# EurocardPowerSupply.net
KiCad netlist of a schematic drawn in EAGLE
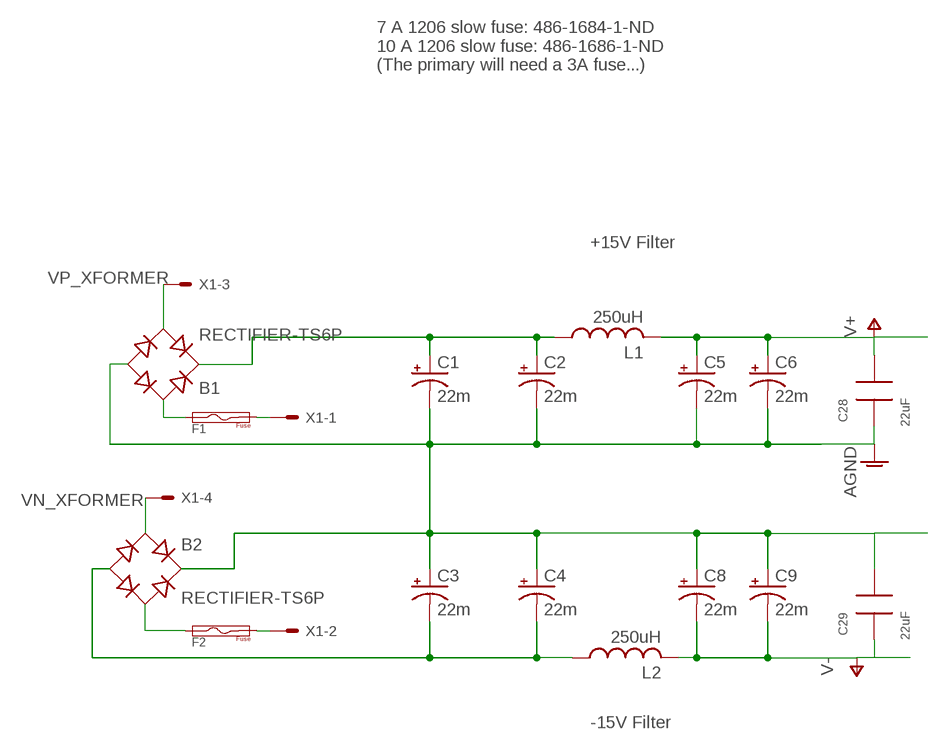
[diagram p0: schematic, sheet 1]
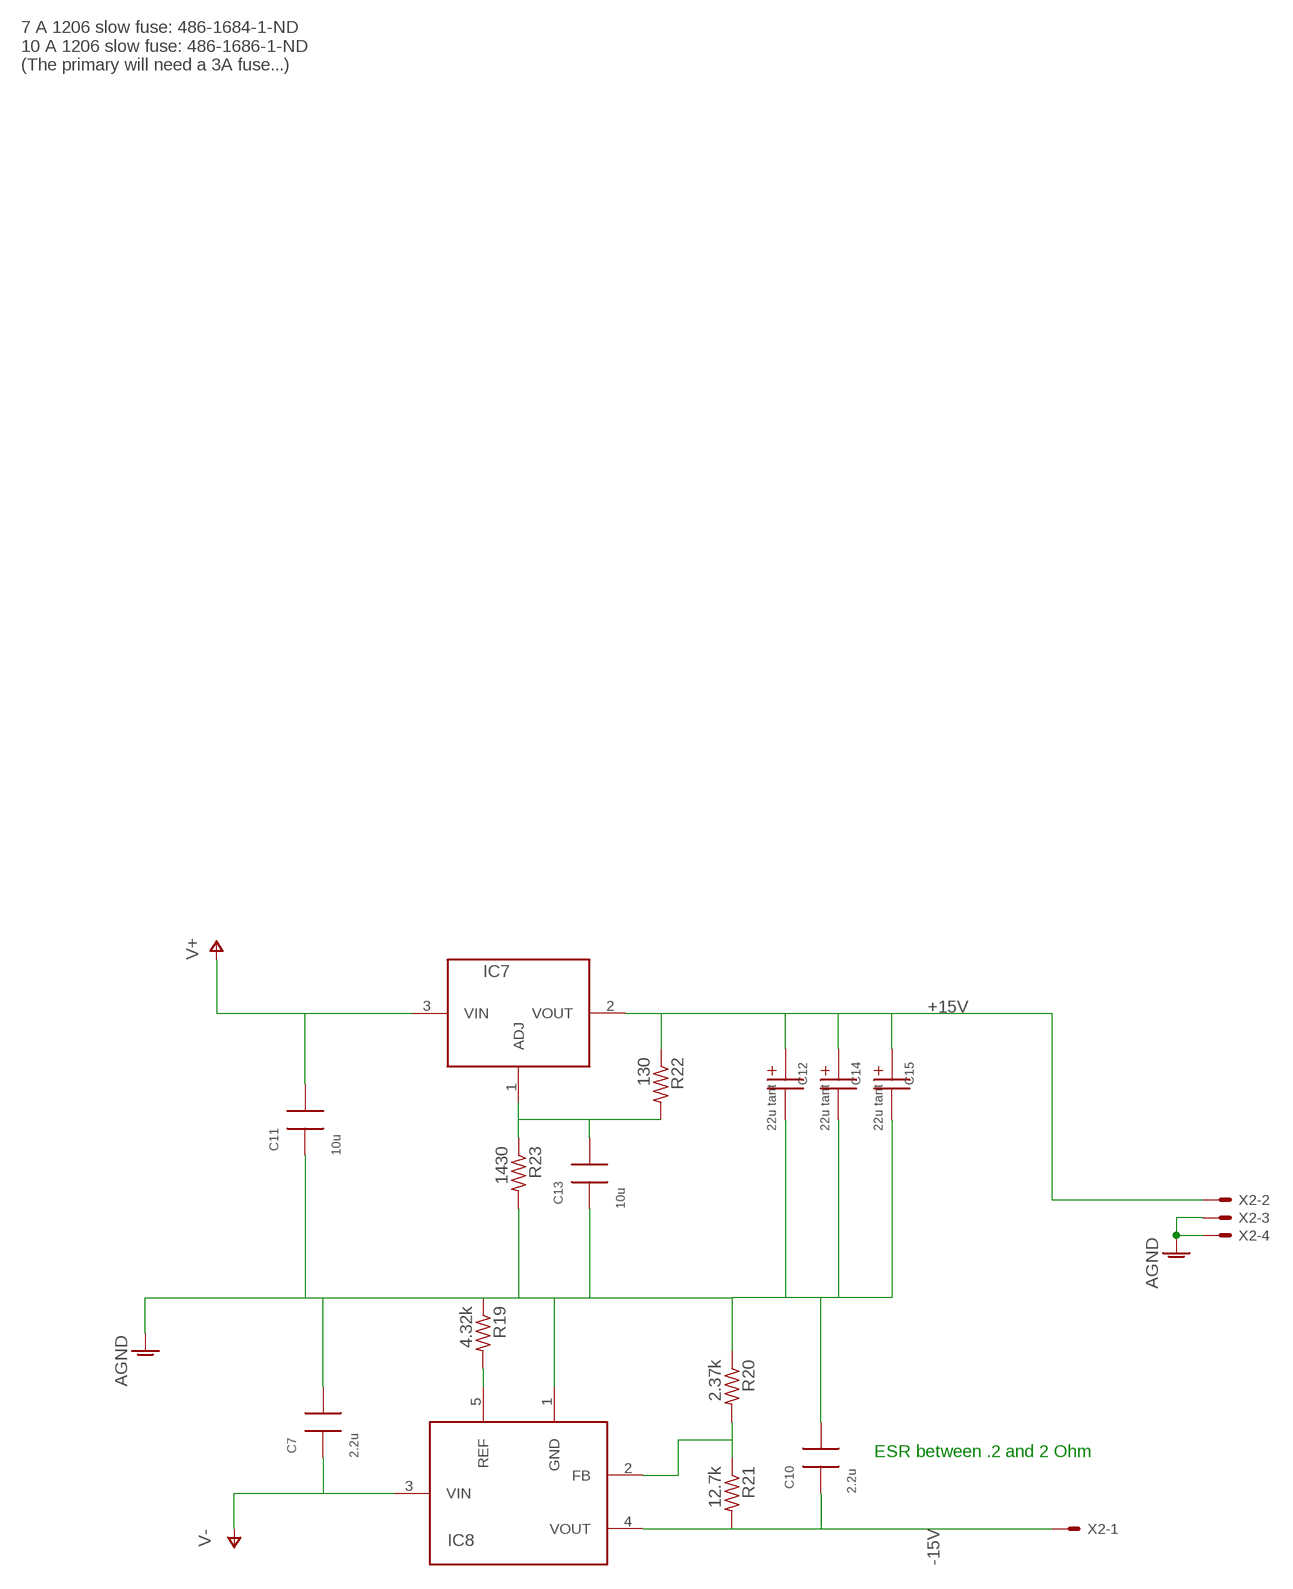
[diagram p1: schematic, sheet 2]
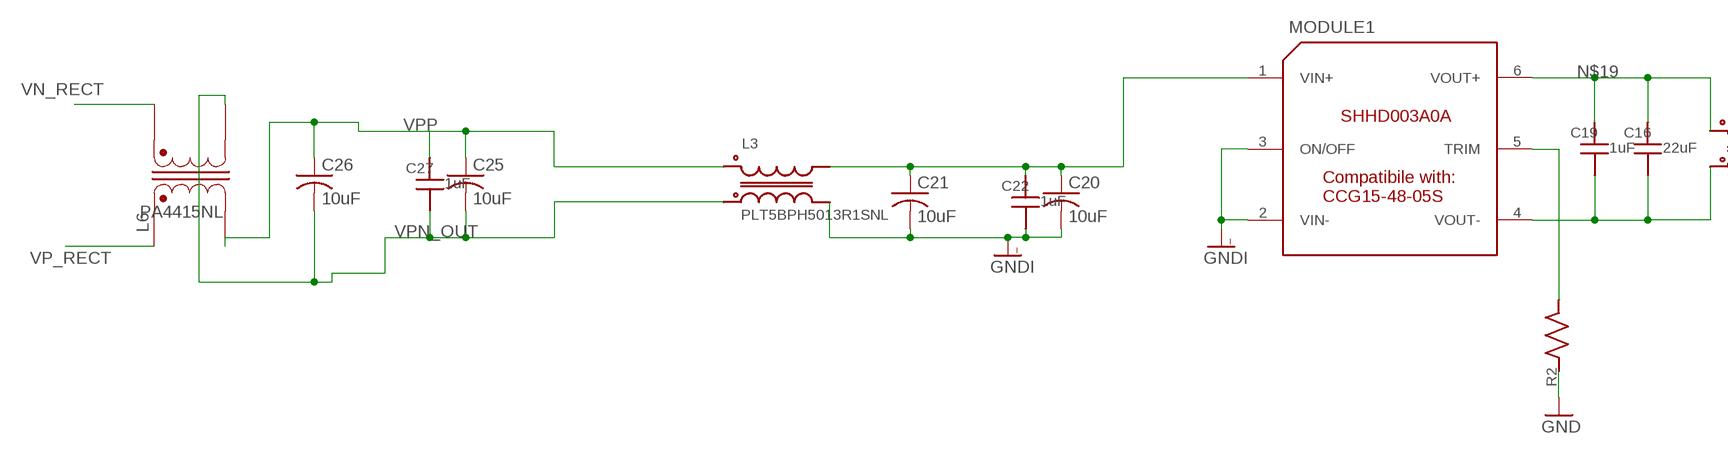
[diagram p2: schematic, sheet 3, part 1 of 2]
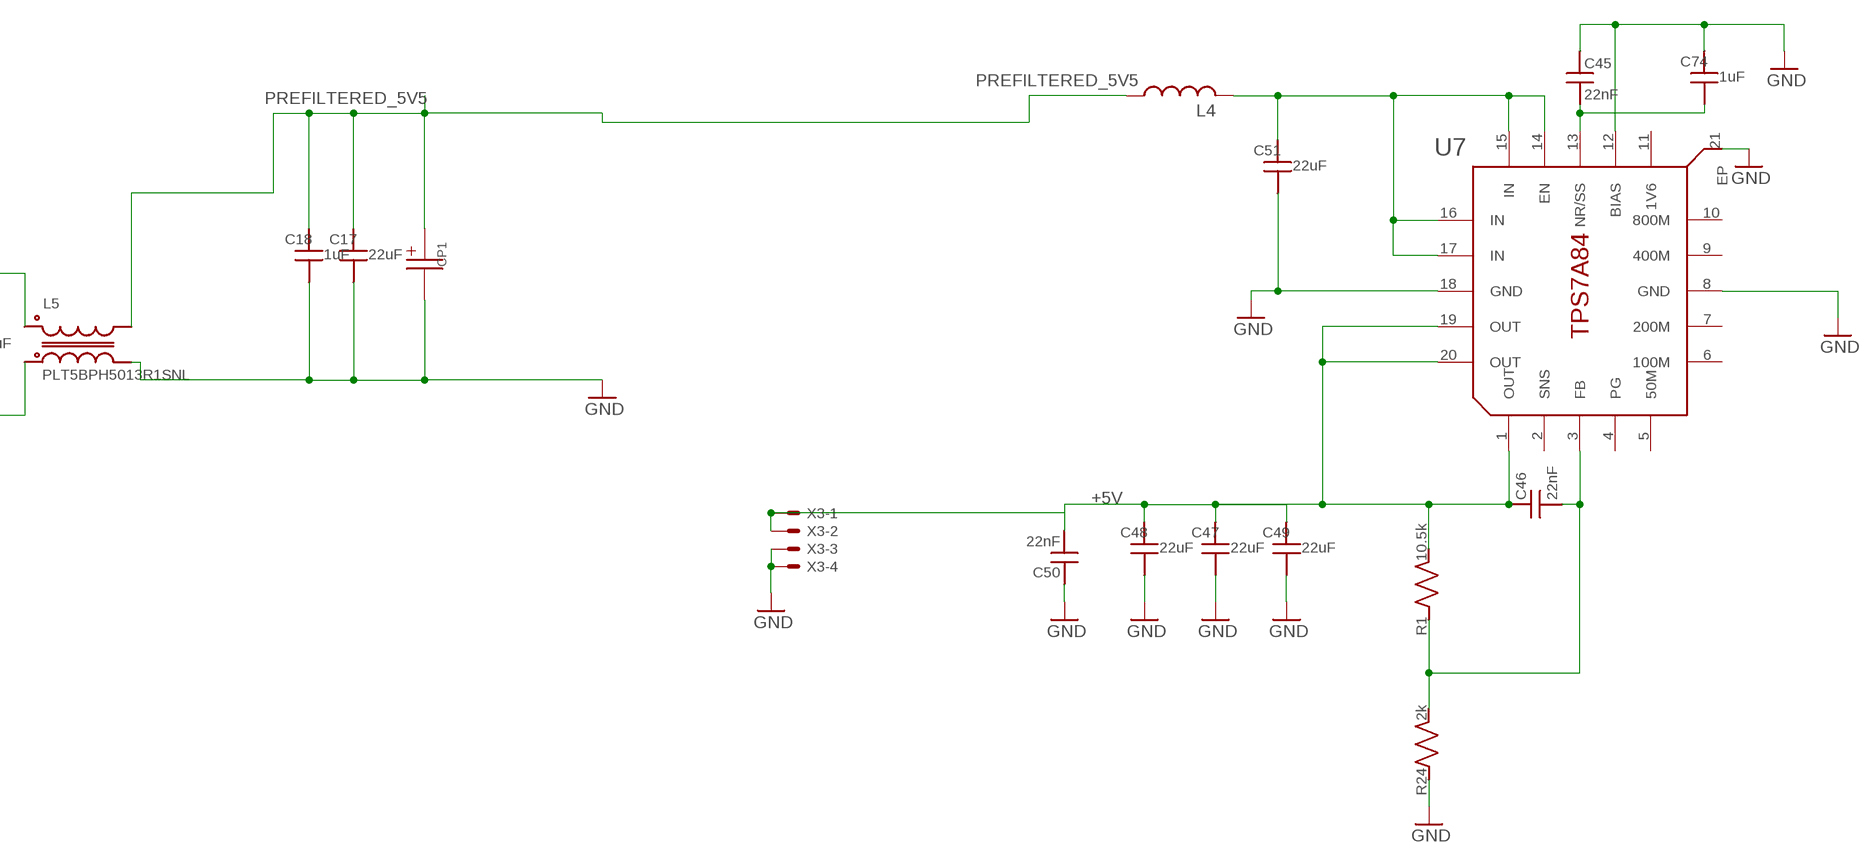
[diagram p3: schematic, sheet 3, part 2 of 2]

(export (version "E")
  (design (tool "Eeschema 10.0.6"))
  (components
    (comp (ref "C16")
      (value "22uF")
      (footprint "eagle-import:C_MLCC_0805")
      (libsource (lib "eagle-import") (part "C_MLCC_SMDCMLCC_0805"))
    )
    (comp (ref "C17")
      (value "22uF")
      (footprint "eagle-import:C_MLCC_0805")
      (libsource (lib "eagle-import") (part "C_MLCC_SMDCMLCC_0805"))
    )
    (comp (ref "C18")
      (value "1uF")
      (footprint "eagle-import:C_MLCC_0805")
      (libsource (lib "eagle-import") (part "C_MLCC_SMDCMLCC_0805"))
    )
    (comp (ref "C19")
      (value "1uF")
      (footprint "eagle-import:C_MLCC_0805")
      (libsource (lib "eagle-import") (part "C_MLCC_SMDCMLCC_0805"))
    )
    (comp (ref "C20")
      (value "10uF")
      (footprint "eagle-import:C2220K")
      (libsource (lib "eagle-import") (part "C-USC2220K"))
    )
    (comp (ref "C21")
      (value "10uF")
      (footprint "eagle-import:C2220K")
      (libsource (lib "eagle-import") (part "C-USC2220K"))
    )
    (comp (ref "C22")
      (value "1uF")
      (footprint "eagle-import:C_MLCC_0805")
      (libsource (lib "eagle-import") (part "C_MLCC_SMDCMLCC_0805"))
    )
    (comp (ref "C25")
      (value "10uF")
      (footprint "eagle-import:C2220K")
      (libsource (lib "eagle-import") (part "C-USC2220K"))
    )
    (comp (ref "C26")
      (value "10uF")
      (footprint "eagle-import:C2220K")
      (libsource (lib "eagle-import") (part "C-USC2220K"))
    )
    (comp (ref "C27")
      (value "1uF")
      (footprint "eagle-import:C_MLCC_0805")
      (libsource (lib "eagle-import") (part "C_MLCC_SMDCMLCC_0805"))
    )
    (comp (ref "C45")
      (value "22nF")
      (footprint "eagle-import:C_MLCC_0306")
      (libsource (lib "eagle-import") (part "C_MLCC_SMDCMLCC_0306"))
    )
    (comp (ref "C46")
      (value "22nF")
      (footprint "eagle-import:C_MLCC_0306")
      (libsource (lib "eagle-import") (part "C_MLCC_SMDCMLCC_0306"))
    )
    (comp (ref "C47")
      (value "22uF")
      (footprint "eagle-import:C_MLCC_0805")
      (libsource (lib "eagle-import") (part "C_MLCC_SMDCMLCC_0805"))
    )
    (comp (ref "C48")
      (value "22uF")
      (footprint "eagle-import:C_MLCC_0805")
      (libsource (lib "eagle-import") (part "C_MLCC_SMDCMLCC_0805"))
    )
    (comp (ref "C49")
      (value "22uF")
      (footprint "eagle-import:C_MLCC_0805")
      (libsource (lib "eagle-import") (part "C_MLCC_SMDCMLCC_0805"))
    )
    (comp (ref "C50")
      (value "22nF")
      (footprint "eagle-import:C_MLCC_0306")
      (libsource (lib "eagle-import") (part "C_MLCC_SMDCMLCC_0306"))
    )
    (comp (ref "C51")
      (value "22uF")
      (footprint "eagle-import:C_MLCC_0805")
      (libsource (lib "eagle-import") (part "C_MLCC_SMDCMLCC_0805"))
    )
    (comp (ref "C74")
      (value "1uF")
      (footprint "eagle-import:C_MLCC_0805")
      (libsource (lib "eagle-import") (part "C_MLCC_SMDCMLCC_0805"))
    )
    (comp (ref "CP1")
      (value "CAP-POLPANASONIC_F")
      (footprint "eagle-import:PANASONIC_F")
      (libsource (lib "eagle-import") (part "CAP-POLPANASONIC_F"))
    )
    (comp (ref "L3")
      (value "PLT5BPH5013R1SNL")
      (footprint "eagle-import:MURATA_CM_CHOKE_PLT5BPH_SERIES")
      (libsource (lib "eagle-import") (part "MURATA_CM_COIL_SERIES_PLT5BPH"))
    )
    (comp (ref "L4")
      (value "MURATA_NFZ5BBW100LN10L")
      (footprint "eagle-import:MURATA_1MHZ_3A_FERRITE")
      (libsource (lib "eagle-import") (part "MURATA_NFZ5BBW100LN10L"))
    )
    (comp (ref "L5")
      (value "PLT5BPH5013R1SNL")
      (footprint "eagle-import:MURATA_CM_CHOKE_PLT5BPH_SERIES")
      (libsource (lib "eagle-import") (part "MURATA_CM_COIL_SERIES_PLT5BPH"))
    )
    (comp (ref "L6")
      (value "PA4415NL")
      (footprint "eagle-import:PA4415NL")
      (libsource (lib "eagle-import") (part "PA4415NL"))
    )
    (comp (ref "MODULE1")
      (value "GE_SHHD003A0A")
      (footprint "eagle-import:GE_SHHD003A0A_THROUGH_HOLE")
      (libsource (lib "eagle-import") (part "GE_SHHD003A0A"))
    )
    (comp (ref "R1")
      (value "10.5k")
      (footprint "eagle-import:R_0805")
      (libsource (lib "eagle-import") (part "R_SMDR0805"))
    )
    (comp (ref "R2")
      (value "R_SMDR0805")
      (footprint "eagle-import:R_0805")
      (libsource (lib "eagle-import") (part "R_SMDR0805"))
    )
    (comp (ref "R24")
      (value "2k")
      (footprint "eagle-import:R_0805")
      (libsource (lib "eagle-import") (part "R_SMDR0805"))
    )
    (comp (ref "U7")
      (value "TEXAS_INSTRUMENTS_TPS7A84")
      (footprint "eagle-import:S-PVQFN-N20")
      (libsource (lib "eagle-import") (part "TEXAS_INSTRUMENTS_TPS7A84"))
    )
    (comp (ref "X3")
      (value "5566-4")
      (footprint "eagle-import:5566-4")
      (libsource (lib "eagle-import") (part "5566-4"))
    )
    (comp (ref "B1")
      (value "RECTIFIER-TS6P")
      (footprint "eagle-import:TS6P")
      (libsource (lib "eagle-import") (part "RECTIFIER-TS6P"))
    )
    (comp (ref "B2")
      (value "RECTIFIER-TS6P")
      (footprint "eagle-import:TS6P")
      (libsource (lib "eagle-import") (part "RECTIFIER-TS6P"))
    )
    (comp (ref "C1")
      (value "22m")
      (footprint "eagle-import:EB35D")
      (libsource (lib "eagle-import") (part "CPOL-USEB35D"))
    )
    (comp (ref "C2")
      (value "22m")
      (footprint "eagle-import:EB35D")
      (libsource (lib "eagle-import") (part "CPOL-USEB35D"))
    )
    (comp (ref "C3")
      (value "22m")
      (footprint "eagle-import:EB35D")
      (libsource (lib "eagle-import") (part "CPOL-USEB35D"))
    )
    (comp (ref "C4")
      (value "22m")
      (footprint "eagle-import:EB35D")
      (libsource (lib "eagle-import") (part "CPOL-USEB35D"))
    )
    (comp (ref "C5")
      (value "22m")
      (footprint "eagle-import:EB35D")
      (libsource (lib "eagle-import") (part "CPOL-USEB35D"))
    )
    (comp (ref "C6")
      (value "22m")
      (footprint "eagle-import:EB35D")
      (libsource (lib "eagle-import") (part "CPOL-USEB35D"))
    )
    (comp (ref "C8")
      (value "22m")
      (footprint "eagle-import:EB35D")
      (libsource (lib "eagle-import") (part "CPOL-USEB35D"))
    )
    (comp (ref "C9")
      (value "22m")
      (footprint "eagle-import:EB35D")
      (libsource (lib "eagle-import") (part "CPOL-USEB35D"))
    )
    (comp (ref "C28")
      (value "22uF")
      (footprint "eagle-import:1206")
      (libsource (lib "eagle-import") (part "CAP1206"))
    )
    (comp (ref "C29")
      (value "22uF")
      (footprint "eagle-import:1206")
      (libsource (lib "eagle-import") (part "CAP1206"))
    )
    (comp (ref "F1")
      (value "FUSE1206")
      (footprint "eagle-import:FUSE1206")
      (libsource (lib "eagle-import") (part "FUSE1206"))
    )
    (comp (ref "F2")
      (value "FUSE1206")
      (footprint "eagle-import:FUSE1206")
      (libsource (lib "eagle-import") (part "FUSE1206"))
    )
    (comp (ref "L1")
      (value "250uH")
      (footprint "eagle-import:5721-RC")
      (libsource (lib "eagle-import") (part "INDUCTOR5721-RC"))
    )
    (comp (ref "L2")
      (value "250uH")
      (footprint "eagle-import:5721-RC")
      (libsource (lib "eagle-import") (part "INDUCTOR5721-RC"))
    )
    (comp (ref "X1")
      (value "5566-4")
      (footprint "eagle-import:5566-4")
      (libsource (lib "eagle-import") (part "5566-4"))
    )
    (comp (ref "C7")
      (value "2.2u")
      (footprint "eagle-import:1206")
      (libsource (lib "eagle-import") (part "CAP1206"))
    )
    (comp (ref "C10")
      (value "2.2u")
      (footprint "eagle-import:1206")
      (libsource (lib "eagle-import") (part "CAP1206"))
    )
    (comp (ref "C11")
      (value "10u")
      (footprint "eagle-import:1206")
      (libsource (lib "eagle-import") (part "CAP1206"))
    )
    (comp (ref "C12")
      (value "22u tant")
      (footprint "eagle-import:1206P")
      (libsource (lib "eagle-import") (part "rlc-jqi_CAP-POL1206"))
    )
    (comp (ref "C13")
      (value "10u")
      (footprint "eagle-import:1206")
      (libsource (lib "eagle-import") (part "CAP1206"))
    )
    (comp (ref "C14")
      (value "22u tant")
      (footprint "eagle-import:1206P")
      (libsource (lib "eagle-import") (part "rlc-jqi_CAP-POL1206"))
    )
    (comp (ref "C15")
      (value "22u tant")
      (footprint "eagle-import:1206P")
      (libsource (lib "eagle-import") (part "rlc-jqi_CAP-POL1206"))
    )
    (comp (ref "IC7")
      (value "LM1084TO220")
      (footprint "eagle-import:T03B")
      (libsource (lib "eagle-import") (part "LM1084TO220"))
    )
    (comp (ref "IC8")
      (value "LT1185TO220/INLINE")
      (footprint "eagle-import:T05A")
      (libsource (lib "eagle-import") (part "LT1185TO220/INLINE"))
    )
    (comp (ref "R19")
      (value "4.32k")
      (footprint "eagle-import:R1206")
      (libsource (lib "eagle-import") (part "R-US_R1206"))
    )
    (comp (ref "R20")
      (value "2.37k")
      (footprint "eagle-import:R1206")
      (libsource (lib "eagle-import") (part "R-US_R1206"))
    )
    (comp (ref "R21")
      (value "12.7k")
      (footprint "eagle-import:R1206")
      (libsource (lib "eagle-import") (part "R-US_R1206"))
    )
    (comp (ref "R22")
      (value "130")
      (footprint "eagle-import:R1206")
      (libsource (lib "eagle-import") (part "R-US_R1206"))
    )
    (comp (ref "R23")
      (value "1430")
      (footprint "eagle-import:R1206")
      (libsource (lib "eagle-import") (part "R-US_R1206"))
    )
    (comp (ref "X2")
      (value "5566-4")
      (footprint "eagle-import:5566-4")
      (libsource (lib "eagle-import") (part "5566-4"))
    )
  )
  (nets
    (net (code "1") (name "+5V") (class "Default")
      (node (ref "C46") (pin "P$1") (pinfunction "1_P$1") (pintype "passive"))
      (node (ref "C47") (pin "P$1") (pinfunction "1_P$1") (pintype "passive"))
      (node (ref "C48") (pin "P$1") (pinfunction "1_P$1") (pintype "passive"))
      (node (ref "C49") (pin "P$1") (pinfunction "1_P$1") (pintype "passive"))
      (node (ref "C50") (pin "P$2") (pinfunction "2_P$2") (pintype "passive"))
      (node (ref "R1") (pin "P$2") (pinfunction "2_P$2") (pintype "passive"))
      (node (ref "U7") (pin "1") (pinfunction "OUT_1") (pintype "bidirectional"))
      (node (ref "U7") (pin "19") (pinfunction "OUT_19") (pintype "bidirectional"))
      (node (ref "U7") (pin "20") (pinfunction "OUT_20") (pintype "bidirectional"))
      (node (ref "X3") (pin "1") (pinfunction "S_1") (pintype "passive"))
      (node (ref "X3") (pin "2") (pinfunction "S_2") (pintype "passive"))
    )
    (net (code "2") (name "+15V") (class "Default")
      (node (ref "C12") (pin "1") (pinfunction "P$1_1") (pintype "passive"))
      (node (ref "C14") (pin "1") (pinfunction "P$1_1") (pintype "passive"))
      (node (ref "C15") (pin "1") (pinfunction "P$1_1") (pintype "passive"))
      (node (ref "IC7") (pin "2") (pinfunction "VOUT_2") (pintype "bidirectional"))
      (node (ref "R22") (pin "1") (pinfunction "1_1") (pintype "passive"))
      (node (ref "X2") (pin "2") (pinfunction "S_2") (pintype "passive"))
    )
    (net (code "3") (name "-15V") (class "Default")
      (node (ref "C10") (pin "1") (pinfunction "P$1_1") (pintype "passive"))
      (node (ref "IC8") (pin "4") (pinfunction "VOUT_4") (pintype "bidirectional"))
      (node (ref "R21") (pin "2") (pinfunction "2_2") (pintype "passive"))
      (node (ref "X2") (pin "1") (pinfunction "S_1") (pintype "passive"))
    )
    (net (code "4") (name "AGND") (class "Default")
      (node (ref "B1") (pin "-") (pinfunction "-_-") (pintype "passive"))
      (node (ref "B2") (pin "+") (pinfunction "+_+") (pintype "passive"))
      (node (ref "C1") (pin "-") (pinfunction "-_-") (pintype "passive"))
      (node (ref "C10") (pin "2") (pinfunction "P$2_2") (pintype "passive"))
      (node (ref "C11") (pin "1") (pinfunction "P$1_1") (pintype "passive"))
      (node (ref "C12") (pin "2") (pinfunction "P$2_2") (pintype "passive"))
      (node (ref "C13") (pin "1") (pinfunction "P$1_1") (pintype "passive"))
      (node (ref "C14") (pin "2") (pinfunction "P$2_2") (pintype "passive"))
      (node (ref "C15") (pin "2") (pinfunction "P$2_2") (pintype "passive"))
      (node (ref "C2") (pin "-") (pinfunction "-_-") (pintype "passive"))
      (node (ref "C28") (pin "1") (pinfunction "P$1_1") (pintype "passive"))
      (node (ref "C29") (pin "2") (pinfunction "P$2_2") (pintype "passive"))
      (node (ref "C3") (pin "+") (pinfunction "+_+") (pintype "passive"))
      (node (ref "C4") (pin "+") (pinfunction "+_+") (pintype "passive"))
      (node (ref "C5") (pin "-") (pinfunction "-_-") (pintype "passive"))
      (node (ref "C6") (pin "-") (pinfunction "-_-") (pintype "passive"))
      (node (ref "C7") (pin "2") (pinfunction "P$2_2") (pintype "passive"))
      (node (ref "C8") (pin "+") (pinfunction "+_+") (pintype "passive"))
      (node (ref "C9") (pin "+") (pinfunction "+_+") (pintype "passive"))
      (node (ref "IC8") (pin "1") (pinfunction "GND_1") (pintype "bidirectional"))
      (node (ref "R19") (pin "1") (pinfunction "1_1") (pintype "passive"))
      (node (ref "R20") (pin "1") (pinfunction "1_1") (pintype "passive"))
      (node (ref "R23") (pin "2") (pinfunction "2_2") (pintype "passive"))
      (node (ref "X2") (pin "3") (pinfunction "S_3") (pintype "passive"))
      (node (ref "X2") (pin "4") (pinfunction "S_4") (pintype "passive"))
    )
    (net (code "5") (name "GND") (class "Default")
      (node (ref "C17") (pin "P$2") (pinfunction "2_P$2") (pintype "passive"))
      (node (ref "C18") (pin "P$2") (pinfunction "2_P$2") (pintype "passive"))
      (node (ref "C45") (pin "P$1") (pinfunction "1_P$1") (pintype "passive"))
      (node (ref "C47") (pin "P$2") (pinfunction "2_P$2") (pintype "passive"))
      (node (ref "C48") (pin "P$2") (pinfunction "2_P$2") (pintype "passive"))
      (node (ref "C49") (pin "P$2") (pinfunction "2_P$2") (pintype "passive"))
      (node (ref "C50") (pin "P$1") (pinfunction "1_P$1") (pintype "passive"))
      (node (ref "C51") (pin "P$2") (pinfunction "2_P$2") (pintype "passive"))
      (node (ref "C74") (pin "P$1") (pinfunction "1_P$1") (pintype "passive"))
      (node (ref "CP1") (pin "-") (pinfunction "P$2_-") (pintype "passive"))
      (node (ref "L5") (pin "P$3") (pinfunction "3_P$3") (pintype "passive"))
      (node (ref "R2") (pin "P$1") (pinfunction "1_P$1") (pintype "passive"))
      (node (ref "R24") (pin "P$1") (pinfunction "1_P$1") (pintype "passive"))
      (node (ref "U7") (pin "12") (pinfunction "BIAS_12") (pintype "bidirectional"))
      (node (ref "U7") (pin "18") (pinfunction "GND_18") (pintype "bidirectional"))
      (node (ref "U7") (pin "21") (pinfunction "EP_21") (pintype "bidirectional"))
      (node (ref "U7") (pin "8") (pinfunction "GND_8") (pintype "bidirectional"))
      (node (ref "X3") (pin "3") (pinfunction "S_3") (pintype "passive"))
      (node (ref "X3") (pin "4") (pinfunction "S_4") (pintype "passive"))
    )
    (net (code "6") (name "GNDI") (class "Default")
      (node (ref "C20") (pin "2") (pinfunction "2_2") (pintype "passive"))
      (node (ref "C21") (pin "2") (pinfunction "2_2") (pintype "passive"))
      (node (ref "C22") (pin "P$2") (pinfunction "2_P$2") (pintype "passive"))
      (node (ref "L3") (pin "P$3") (pinfunction "3_P$3") (pintype "passive"))
      (node (ref "MODULE1") (pin "2") (pinfunction "VIN-_2") (pintype "bidirectional"))
      (node (ref "MODULE1") (pin "3") (pinfunction "ON/OFF_3") (pintype "bidirectional"))
    )
    (net (code "7") (name "N$19") (class "Default")
      (node (ref "C16") (pin "P$1") (pinfunction "1_P$1") (pintype "passive"))
      (node (ref "C19") (pin "P$1") (pinfunction "1_P$1") (pintype "passive"))
      (node (ref "L5") (pin "P$1") (pinfunction "2_P$1") (pintype "passive"))
      (node (ref "MODULE1") (pin "6") (pinfunction "VOUT+_6") (pintype "bidirectional"))
    )
    (net (code "8") (name "Net-(C13-P$2)") (class "Default")
      (node (ref "C13") (pin "2") (pinfunction "P$2_2") (pintype "passive"))
      (node (ref "IC7") (pin "1") (pinfunction "ADJ_1") (pintype "bidirectional"))
      (node (ref "R22") (pin "2") (pinfunction "2_2") (pintype "passive"))
      (node (ref "R23") (pin "1") (pinfunction "1_1") (pintype "passive"))
    )
    (net (code "9") (name "Net-(C16-2)") (class "Default")
      (node (ref "C16") (pin "P$2") (pinfunction "2_P$2") (pintype "passive"))
      (node (ref "C19") (pin "P$2") (pinfunction "2_P$2") (pintype "passive"))
      (node (ref "L5") (pin "P$4") (pinfunction "1_P$4") (pintype "passive"))
      (node (ref "MODULE1") (pin "4") (pinfunction "VOUT-_4") (pintype "bidirectional"))
    )
    (net (code "10") (name "Net-(C22-1)") (class "Default")
      (node (ref "C20") (pin "1") (pinfunction "1_1") (pintype "passive"))
      (node (ref "C21") (pin "1") (pinfunction "1_1") (pintype "passive"))
      (node (ref "C22") (pin "P$1") (pinfunction "1_P$1") (pintype "passive"))
      (node (ref "L3") (pin "P$2") (pinfunction "4_P$2") (pintype "passive"))
      (node (ref "MODULE1") (pin "1") (pinfunction "VIN+_1") (pintype "bidirectional"))
    )
    (net (code "11") (name "Net-(C45-2)") (class "Default")
      (node (ref "C45") (pin "P$2") (pinfunction "2_P$2") (pintype "passive"))
      (node (ref "C74") (pin "P$2") (pinfunction "2_P$2") (pintype "passive"))
      (node (ref "U7") (pin "13") (pinfunction "NR/SS_13") (pintype "bidirectional"))
    )
    (net (code "12") (name "Net-(C46-2)") (class "Default")
      (node (ref "C46") (pin "P$2") (pinfunction "2_P$2") (pintype "passive"))
      (node (ref "R1") (pin "P$1") (pinfunction "1_P$1") (pintype "passive"))
      (node (ref "R24") (pin "P$2") (pinfunction "2_P$2") (pintype "passive"))
      (node (ref "U7") (pin "3") (pinfunction "FB_3") (pintype "bidirectional"))
    )
    (net (code "13") (name "Net-(C51-1)") (class "Default")
      (node (ref "C51") (pin "P$1") (pinfunction "1_P$1") (pintype "passive"))
      (node (ref "L4") (pin "P$2") (pinfunction "2_P$2") (pintype "passive"))
      (node (ref "U7") (pin "14") (pinfunction "EN_14") (pintype "bidirectional"))
      (node (ref "U7") (pin "15") (pinfunction "IN_15") (pintype "bidirectional"))
      (node (ref "U7") (pin "16") (pinfunction "IN_16") (pintype "bidirectional"))
      (node (ref "U7") (pin "17") (pinfunction "IN_17") (pintype "bidirectional"))
    )
    (net (code "14") (name "Net-(F1-P$1)") (class "Default")
      (node (ref "B1") (pin "AC1") (pinfunction "AC1_AC1") (pintype "passive"))
      (node (ref "F1") (pin "1") (pinfunction "P$1_1") (pintype "bidirectional"))
    )
    (net (code "15") (name "Net-(F1-P$2)") (class "Default")
      (node (ref "F1") (pin "2") (pinfunction "P$2_2") (pintype "bidirectional"))
      (node (ref "X1") (pin "1") (pinfunction "S_1") (pintype "passive"))
    )
    (net (code "16") (name "Net-(F2-P$1)") (class "Default")
      (node (ref "B2") (pin "AC2") (pinfunction "AC2_AC2") (pintype "passive"))
      (node (ref "F2") (pin "1") (pinfunction "P$1_1") (pintype "bidirectional"))
    )
    (net (code "17") (name "Net-(F2-P$2)") (class "Default")
      (node (ref "F2") (pin "2") (pinfunction "P$2_2") (pintype "bidirectional"))
      (node (ref "X1") (pin "2") (pinfunction "S_2") (pintype "passive"))
    )
    (net (code "18") (name "Net-(IC8-FB)") (class "Default")
      (node (ref "IC8") (pin "2") (pinfunction "FB_2") (pintype "bidirectional"))
      (node (ref "R20") (pin "2") (pinfunction "2_2") (pintype "passive"))
      (node (ref "R21") (pin "1") (pinfunction "1_1") (pintype "passive"))
    )
    (net (code "19") (name "Net-(IC8-REF)") (class "Default")
      (node (ref "IC8") (pin "5") (pinfunction "REF_5") (pintype "bidirectional"))
      (node (ref "R19") (pin "2") (pinfunction "2_2") (pintype "passive"))
    )
    (net (code "20") (name "Net-(MODULE1-TRIM)") (class "Default")
      (node (ref "MODULE1") (pin "5") (pinfunction "TRIM_5") (pintype "bidirectional"))
      (node (ref "R2") (pin "P$2") (pinfunction "2_P$2") (pintype "passive"))
    )
    (net (code "21") (name "PREFILTERED_5V5") (class "Default")
      (node (ref "C17") (pin "P$1") (pinfunction "1_P$1") (pintype "passive"))
      (node (ref "C18") (pin "P$1") (pinfunction "1_P$1") (pintype "passive"))
      (node (ref "CP1") (pin "+") (pinfunction "P$1_+") (pintype "passive"))
      (node (ref "L4") (pin "P$1") (pinfunction "1_P$1") (pintype "passive"))
      (node (ref "L5") (pin "P$2") (pinfunction "4_P$2") (pintype "passive"))
    )
    (net (code "22") (name "V+") (class "Default")
      (node (ref "C11") (pin "2") (pinfunction "P$2_2") (pintype "passive"))
      (node (ref "C28") (pin "2") (pinfunction "P$2_2") (pintype "passive"))
      (node (ref "C5") (pin "+") (pinfunction "+_+") (pintype "passive"))
      (node (ref "C6") (pin "+") (pinfunction "+_+") (pintype "passive"))
      (node (ref "IC7") (pin "3") (pinfunction "VIN_3") (pintype "bidirectional"))
      (node (ref "L1") (pin "P$2") (pinfunction "2_P$2") (pintype "passive"))
    )
    (net (code "23") (name "V-") (class "Default")
      (node (ref "C29") (pin "1") (pinfunction "P$1_1") (pintype "passive"))
      (node (ref "C7") (pin "1") (pinfunction "P$1_1") (pintype "passive"))
      (node (ref "C8") (pin "-") (pinfunction "-_-") (pintype "passive"))
      (node (ref "C9") (pin "-") (pinfunction "-_-") (pintype "passive"))
      (node (ref "IC8") (pin "3") (pinfunction "VIN_3") (pintype "bidirectional"))
      (node (ref "L2") (pin "P$2") (pinfunction "2_P$2") (pintype "passive"))
    )
    (net (code "24") (name "VN_RECT") (class "Default")
      (node (ref "B2") (pin "-") (pinfunction "-_-") (pintype "passive"))
      (node (ref "C3") (pin "-") (pinfunction "-_-") (pintype "passive"))
      (node (ref "C4") (pin "-") (pinfunction "-_-") (pintype "passive"))
      (node (ref "L2") (pin "P$1") (pinfunction "1_P$1") (pintype "passive"))
      (node (ref "L6") (pin "2") (pinfunction "2_2") (pintype "bidirectional"))
    )
    (net (code "25") (name "VN_XFORMER") (class "Default")
      (node (ref "B2") (pin "AC1") (pinfunction "AC1_AC1") (pintype "passive"))
      (node (ref "X1") (pin "4") (pinfunction "S_4") (pintype "passive"))
    )
    (net (code "26") (name "VPN_OUT") (class "Default")
      (node (ref "C25") (pin "2") (pinfunction "2_2") (pintype "passive"))
      (node (ref "C26") (pin "2") (pinfunction "2_2") (pintype "passive"))
      (node (ref "C27") (pin "P$2") (pinfunction "2_P$2") (pintype "passive"))
      (node (ref "L3") (pin "P$4") (pinfunction "1_P$4") (pintype "passive"))
      (node (ref "L6") (pin "3") (pinfunction "4_3") (pintype "bidirectional"))
    )
    (net (code "27") (name "VPP") (class "Default")
      (node (ref "C25") (pin "1") (pinfunction "1_1") (pintype "passive"))
      (node (ref "C26") (pin "1") (pinfunction "1_1") (pintype "passive"))
      (node (ref "C27") (pin "P$1") (pinfunction "1_P$1") (pintype "passive"))
      (node (ref "L3") (pin "P$1") (pinfunction "2_P$1") (pintype "passive"))
      (node (ref "L6") (pin "4") (pinfunction "3_4") (pintype "bidirectional"))
    )
    (net (code "28") (name "VP_RECT") (class "Default")
      (node (ref "B1") (pin "+") (pinfunction "+_+") (pintype "passive"))
      (node (ref "C1") (pin "+") (pinfunction "+_+") (pintype "passive"))
      (node (ref "C2") (pin "+") (pinfunction "+_+") (pintype "passive"))
      (node (ref "L1") (pin "P$1") (pinfunction "1_P$1") (pintype "passive"))
      (node (ref "L6") (pin "1") (pinfunction "1_1") (pintype "bidirectional"))
    )
    (net (code "29") (name "VP_XFORMER") (class "Default")
      (node (ref "B1") (pin "AC2") (pinfunction "AC2_AC2") (pintype "passive"))
      (node (ref "X1") (pin "3") (pinfunction "S_3") (pintype "passive"))
    )
    (net (code "30") (name "unconnected-(U7-1V6-Pad11)") (class "Default")
      (node (ref "U7") (pin "11") (pinfunction "1V6_11") (pintype "bidirectional"))
    )
    (net (code "31") (name "unconnected-(U7-50M-Pad5)") (class "Default")
      (node (ref "U7") (pin "5") (pinfunction "50M_5") (pintype "bidirectional"))
    )
    (net (code "32") (name "unconnected-(U7-100M-Pad6)") (class "Default")
      (node (ref "U7") (pin "6") (pinfunction "100M_6") (pintype "bidirectional"))
    )
    (net (code "33") (name "unconnected-(U7-200M-Pad7)") (class "Default")
      (node (ref "U7") (pin "7") (pinfunction "200M_7") (pintype "bidirectional"))
    )
    (net (code "34") (name "unconnected-(U7-400M-Pad9)") (class "Default")
      (node (ref "U7") (pin "9") (pinfunction "400M_9") (pintype "bidirectional"))
    )
    (net (code "35") (name "unconnected-(U7-800M-Pad10)") (class "Default")
      (node (ref "U7") (pin "10") (pinfunction "800M_10") (pintype "bidirectional"))
    )
    (net (code "36") (name "unconnected-(U7-PG-Pad4)") (class "Default")
      (node (ref "U7") (pin "4") (pinfunction "PG_4") (pintype "bidirectional"))
    )
    (net (code "37") (name "unconnected-(U7-SNS-Pad2)") (class "Default")
      (node (ref "U7") (pin "2") (pinfunction "SNS_2") (pintype "bidirectional"))
    )
  )
)
